# Irrigatron.net
KiCad netlist of a schematic drawn in EasyEDA
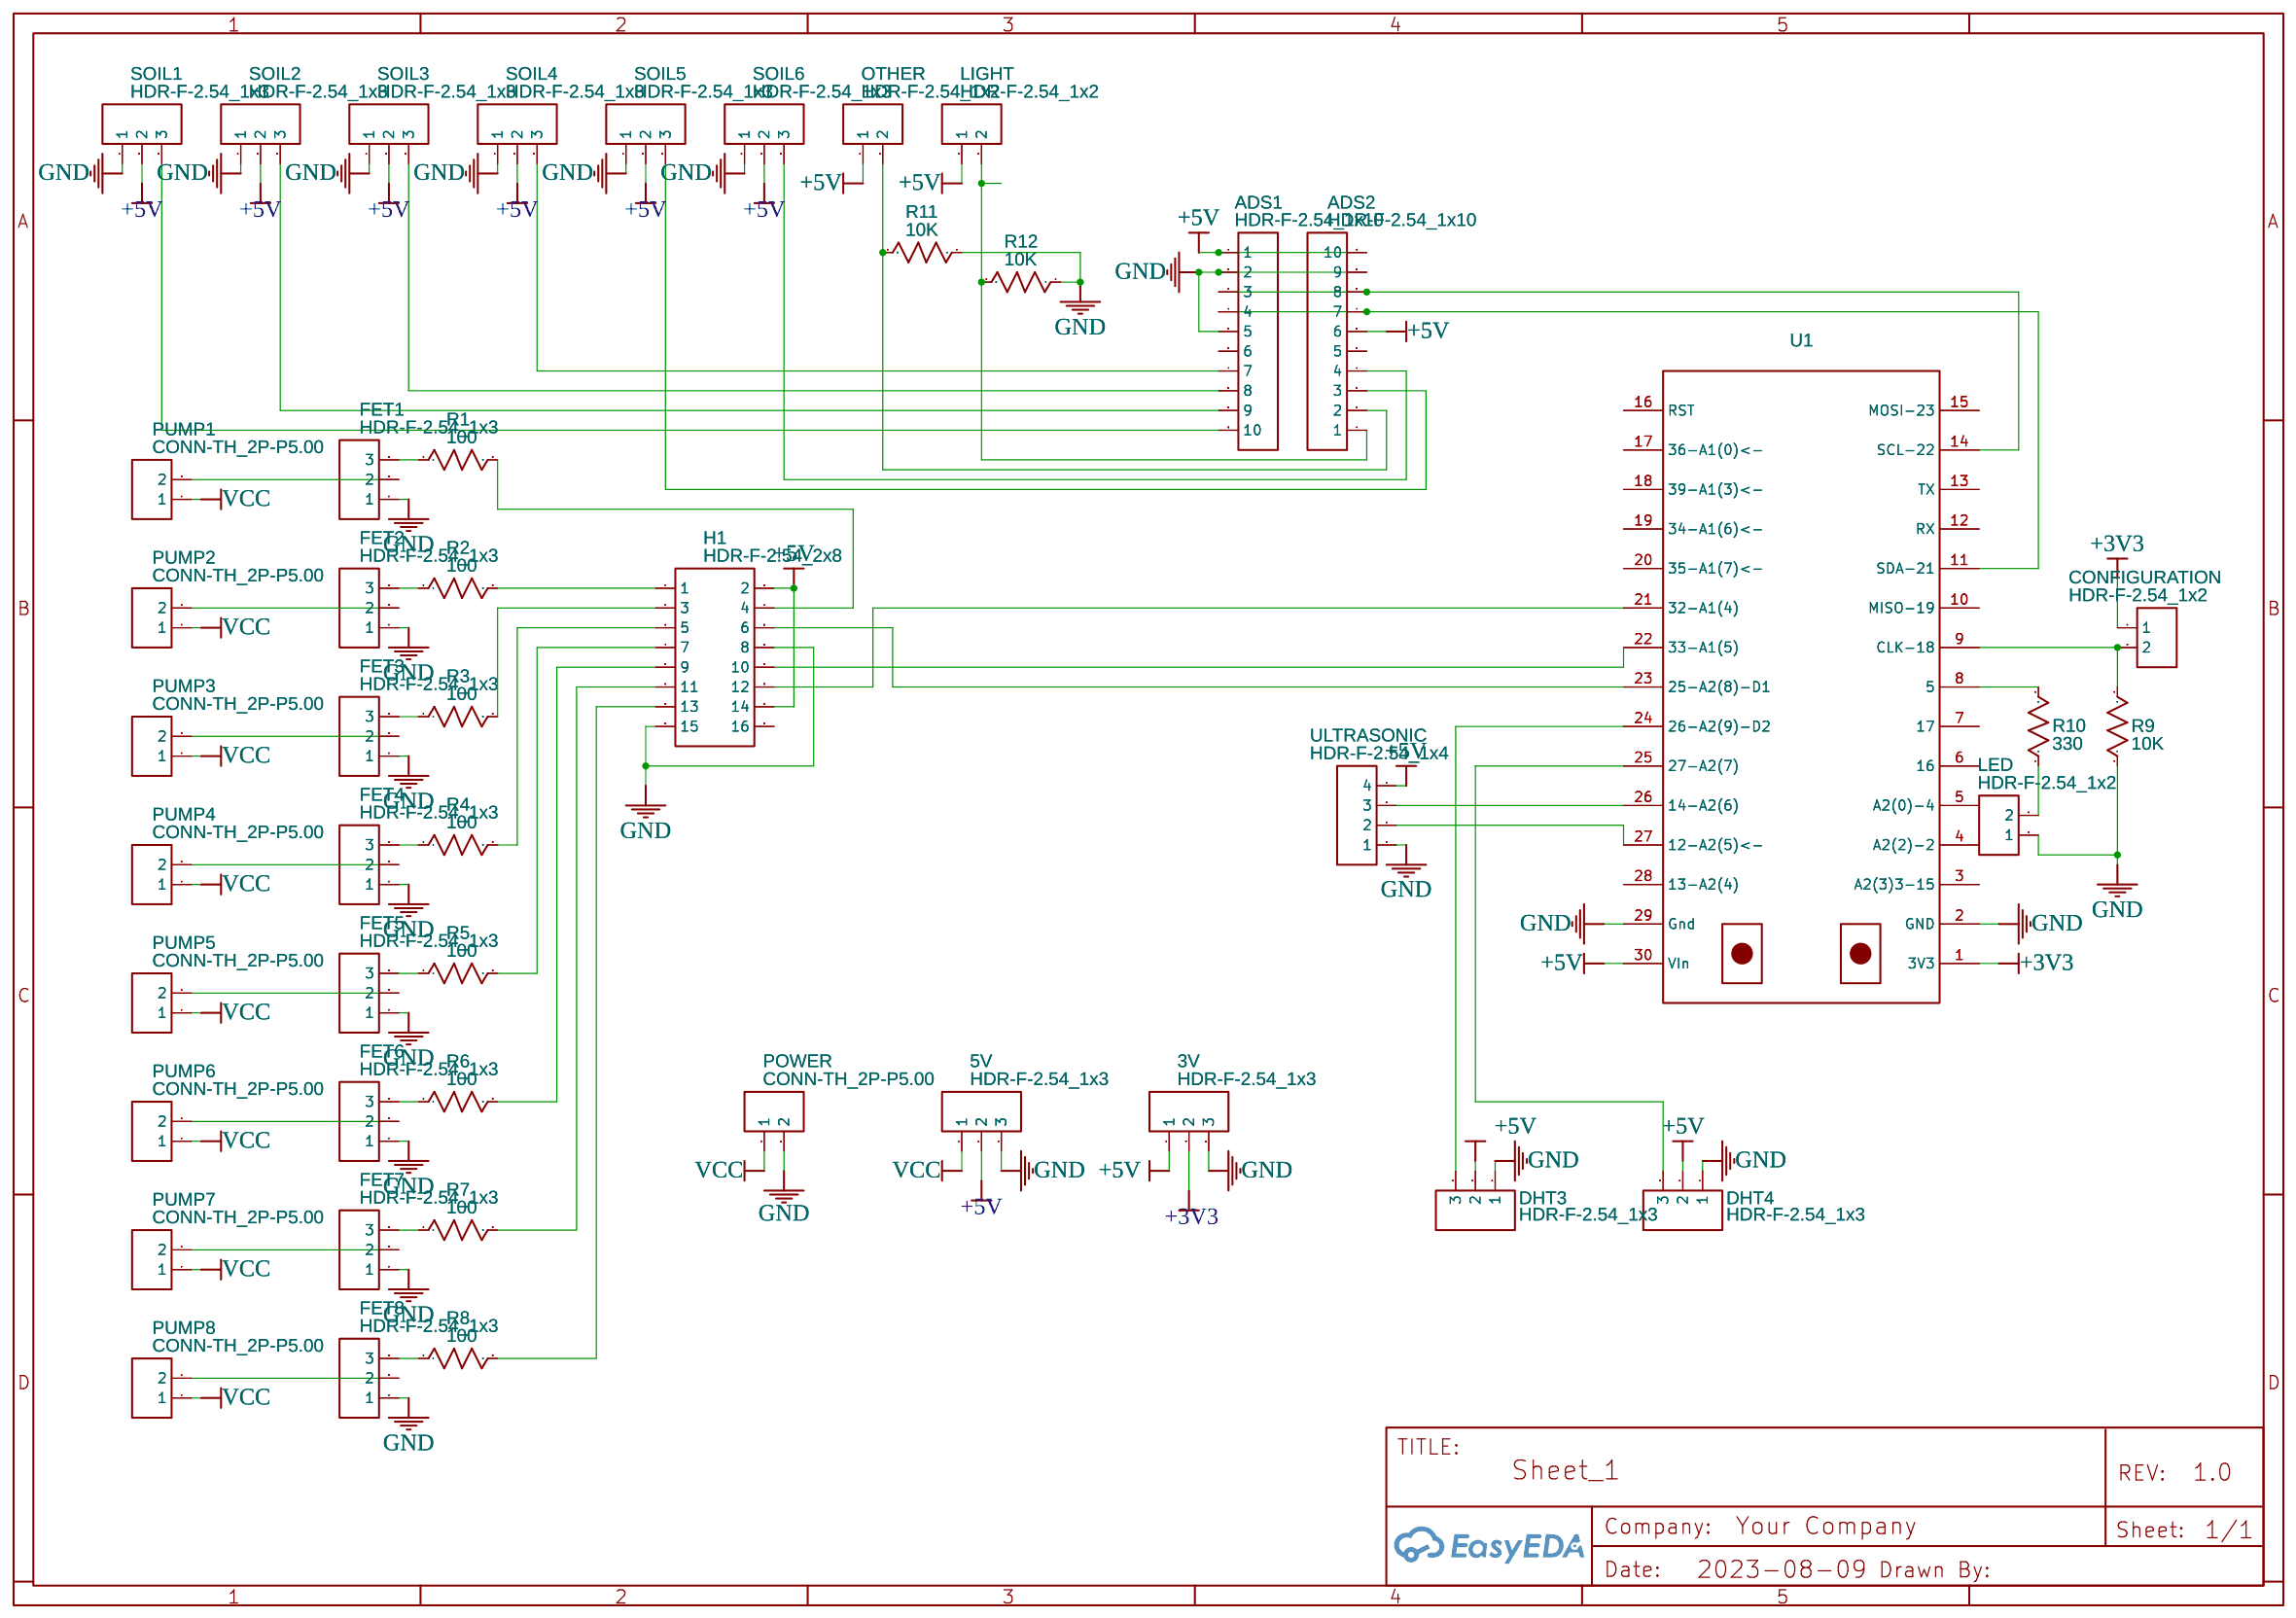
[diagram p0: schematic sheet]

(export (version "E")
  (design (tool "Eeschema 10.0.6"))
  (components
    (comp (ref "3V") (value "HDR-F-2.54_1x3") (libsource (lib "") (part "HDR-F-2.54_1x3_4")))
    (comp (ref "5V") (value "HDR-F-2.54_1x3") (libsource (lib "") (part "HDR-F-2.54_1x3_2")))
    (comp (ref "ADS1") (value "HDR-F-2.54_1x10") (libsource (lib "") (part "HDR-F-2.54_1x10_1")))
    (comp (ref "ADS2") (value "HDR-F-2.54_1x10") (libsource (lib "") (part "HDR-F-2.54_1x10")))
    (comp (ref "CONFIGURATION") (value "HDR-F-2.54_1x2") (libsource (lib "") (part "HDR-F-2.54_1x2_2")))
    (comp (ref "DHT3") (value "HDR-F-2.54_1x3") (libsource (lib "") (part "HDR-F-2.54_1x3")))
    (comp (ref "DHT4") (value "HDR-F-2.54_1x3") (libsource (lib "") (part "HDR-F-2.54_1x3")))
    (comp (ref "FET1") (value "HDR-F-2.54_1x3") (libsource (lib "") (part "HDR-F-2.54_1x3_3")))
    (comp (ref "FET2") (value "HDR-F-2.54_1x3") (libsource (lib "") (part "HDR-F-2.54_1x3_3")))
    (comp (ref "FET3") (value "HDR-F-2.54_1x3") (libsource (lib "") (part "HDR-F-2.54_1x3_3")))
    (comp (ref "FET4") (value "HDR-F-2.54_1x3") (libsource (lib "") (part "HDR-F-2.54_1x3_3")))
    (comp (ref "FET5") (value "HDR-F-2.54_1x3") (libsource (lib "") (part "HDR-F-2.54_1x3_3")))
    (comp (ref "FET6") (value "HDR-F-2.54_1x3") (libsource (lib "") (part "HDR-F-2.54_1x3_3")))
    (comp (ref "FET7") (value "HDR-F-2.54_1x3") (libsource (lib "") (part "HDR-F-2.54_1x3_3")))
    (comp (ref "FET8") (value "HDR-F-2.54_1x3") (libsource (lib "") (part "HDR-F-2.54_1x3_3")))
    (comp (ref "H1") (value "HDR-F-2.54_2x8") (libsource (lib "") (part "HDR-F-2.54_2x8")))
    (comp (ref "LED") (value "HDR-F-2.54_1x2") (libsource (lib "") (part "HDR-F-2.54_1x2")))
    (comp (ref "LIGHT") (value "HDR-F-2.54_1x2") (libsource (lib "") (part "HDR-F-2.54_1x2_1")))
    (comp (ref "OTHER") (value "HDR-F-2.54_1x2") (libsource (lib "") (part "HDR-F-2.54_1x2_3")))
    (comp (ref "POWER") (value "CONN-TH_2P-P5.00") (libsource (lib "") (part "CONN-TH_2P-P5.00_1")))
    (comp (ref "PUMP1") (value "CONN-TH_2P-P5.00") (libsource (lib "") (part "CONN-TH_2P-P5.00")))
    (comp (ref "PUMP2") (value "CONN-TH_2P-P5.00") (libsource (lib "") (part "CONN-TH_2P-P5.00")))
    (comp (ref "PUMP3") (value "CONN-TH_2P-P5.00") (libsource (lib "") (part "CONN-TH_2P-P5.00")))
    (comp (ref "PUMP4") (value "CONN-TH_2P-P5.00") (libsource (lib "") (part "CONN-TH_2P-P5.00")))
    (comp (ref "PUMP5") (value "CONN-TH_2P-P5.00") (libsource (lib "") (part "CONN-TH_2P-P5.00")))
    (comp (ref "PUMP6") (value "CONN-TH_2P-P5.00") (libsource (lib "") (part "CONN-TH_2P-P5.00")))
    (comp (ref "PUMP7") (value "CONN-TH_2P-P5.00") (libsource (lib "") (part "CONN-TH_2P-P5.00")))
    (comp (ref "PUMP8") (value "CONN-TH_2P-P5.00") (libsource (lib "") (part "CONN-TH_2P-P5.00")))
    (comp (ref "R1") (value "100") (libsource (lib "") (part "R_0603_US")))
    (comp (ref "R2") (value "100") (libsource (lib "") (part "R_0603_US")))
    (comp (ref "R3") (value "100") (libsource (lib "") (part "R_0603_US")))
    (comp (ref "R4") (value "100") (libsource (lib "") (part "R_0603_US")))
    (comp (ref "R5") (value "100") (libsource (lib "") (part "R_0603_US")))
    (comp (ref "R6") (value "100") (libsource (lib "") (part "R_0603_US")))
    (comp (ref "R7") (value "100") (libsource (lib "") (part "R_0603_US")))
    (comp (ref "R8") (value "100") (libsource (lib "") (part "R_0603_US")))
    (comp (ref "R9") (value "10K") (libsource (lib "") (part "R_0603_US_1")))
    (comp (ref "R10") (value "330") (libsource (lib "") (part "R_0603_US_1")))
    (comp (ref "R11") (value "10K") (libsource (lib "") (part "R_0603_US_2")))
    (comp (ref "R12") (value "10K") (libsource (lib "") (part "R_0603_US_2")))
    (comp (ref "SOIL1") (value "HDR-F-2.54_1x3") (libsource (lib "") (part "HDR-F-2.54_1x3_1")))
    (comp (ref "SOIL2") (value "HDR-F-2.54_1x3") (libsource (lib "") (part "HDR-F-2.54_1x3_1")))
    (comp (ref "SOIL3") (value "HDR-F-2.54_1x3") (libsource (lib "") (part "HDR-F-2.54_1x3_1")))
    (comp (ref "SOIL4") (value "HDR-F-2.54_1x3") (libsource (lib "") (part "HDR-F-2.54_1x3_1")))
    (comp (ref "SOIL5") (value "HDR-F-2.54_1x3") (libsource (lib "") (part "HDR-F-2.54_1x3_1")))
    (comp (ref "SOIL6") (value "HDR-F-2.54_1x3") (libsource (lib "") (part "HDR-F-2.54_1x3_1")))
    (comp (ref "U1") (value "NO") (libsource (lib "") (part "DOIT ESP32 DEVKIT V1 (30pins)")))
    (comp (ref "ULTRASONIC") (value "HDR-F-2.54_1x4") (libsource (lib "") (part "HDR-F-2.54_1x4")))
  )
  (nets
    (net (code "1") (name "+3V3") (class "Default")
      (node (ref "3V") (pin "2") (pinfunction "2_2") (pintype "input"))
      (node (ref "CONFIGURATION") (pin "1") (pinfunction "1_1") (pintype "input"))
      (node (ref "U1") (pin "1") (pinfunction "3V3_1") (pintype "unspecified"))
    )
    (net (code "2") (name "+5V") (class "Default")
      (node (ref "3V") (pin "1") (pinfunction "1_1") (pintype "input"))
      (node (ref "5V") (pin "2") (pinfunction "2_2") (pintype "input"))
      (node (ref "ADS1") (pin "1") (pinfunction "1_1") (pintype "unspecified"))
      (node (ref "ADS2") (pin "10") (pinfunction "10_10") (pintype "unspecified"))
      (node (ref "ADS2") (pin "6") (pinfunction "6_6") (pintype "unspecified"))
      (node (ref "DHT3") (pin "2") (pinfunction "2_2") (pintype "input"))
      (node (ref "DHT4") (pin "2") (pinfunction "2_2") (pintype "input"))
      (node (ref "H1") (pin "14") (pinfunction "14_14") (pintype "input"))
      (node (ref "H1") (pin "2") (pinfunction "2_2") (pintype "input"))
      (node (ref "LIGHT") (pin "1") (pinfunction "1_1") (pintype "input"))
      (node (ref "OTHER") (pin "1") (pinfunction "1_1") (pintype "input"))
      (node (ref "SOIL1") (pin "2") (pinfunction "2_2") (pintype "input"))
      (node (ref "SOIL2") (pin "2") (pinfunction "2_2") (pintype "input"))
      (node (ref "SOIL3") (pin "2") (pinfunction "2_2") (pintype "input"))
      (node (ref "SOIL4") (pin "2") (pinfunction "2_2") (pintype "input"))
      (node (ref "SOIL5") (pin "2") (pinfunction "2_2") (pintype "input"))
      (node (ref "SOIL6") (pin "2") (pinfunction "2_2") (pintype "input"))
      (node (ref "U1") (pin "30") (pinfunction "VIn_30") (pintype "unspecified"))
      (node (ref "ULTRASONIC") (pin "4") (pinfunction "4_4") (pintype "unspecified"))
    )
    (net (code "3") (name "GND") (class "Default")
      (node (ref "3V") (pin "3") (pinfunction "3_3") (pintype "input"))
      (node (ref "5V") (pin "3") (pinfunction "3_3") (pintype "input"))
      (node (ref "ADS1") (pin "2") (pinfunction "2_2") (pintype "unspecified"))
      (node (ref "ADS1") (pin "5") (pinfunction "5_5") (pintype "unspecified"))
      (node (ref "ADS2") (pin "9") (pinfunction "9_9") (pintype "unspecified"))
      (node (ref "DHT3") (pin "1") (pinfunction "1_1") (pintype "input"))
      (node (ref "DHT4") (pin "1") (pinfunction "1_1") (pintype "input"))
      (node (ref "FET1") (pin "1") (pinfunction "1_1") (pintype "input"))
      (node (ref "FET2") (pin "1") (pinfunction "1_1") (pintype "input"))
      (node (ref "FET3") (pin "1") (pinfunction "1_1") (pintype "input"))
      (node (ref "FET4") (pin "1") (pinfunction "1_1") (pintype "input"))
      (node (ref "FET5") (pin "1") (pinfunction "1_1") (pintype "input"))
      (node (ref "FET6") (pin "1") (pinfunction "1_1") (pintype "input"))
      (node (ref "FET7") (pin "1") (pinfunction "1_1") (pintype "input"))
      (node (ref "FET8") (pin "1") (pinfunction "1_1") (pintype "input"))
      (node (ref "H1") (pin "15") (pinfunction "15_15") (pintype "input"))
      (node (ref "H1") (pin "8") (pinfunction "8_8") (pintype "input"))
      (node (ref "LED") (pin "1") (pinfunction "1_1") (pintype "input"))
      (node (ref "POWER") (pin "2") (pinfunction "2_2") (pintype "unspecified"))
      (node (ref "R11") (pin "1") (pinfunction "1_1") (pintype "unspecified"))
      (node (ref "R12") (pin "1") (pinfunction "1_1") (pintype "unspecified"))
      (node (ref "R9") (pin "1") (pinfunction "1_1") (pintype "unspecified"))
      (node (ref "SOIL1") (pin "1") (pinfunction "1_1") (pintype "input"))
      (node (ref "SOIL2") (pin "1") (pinfunction "1_1") (pintype "input"))
      (node (ref "SOIL3") (pin "1") (pinfunction "1_1") (pintype "input"))
      (node (ref "SOIL4") (pin "1") (pinfunction "1_1") (pintype "input"))
      (node (ref "SOIL5") (pin "1") (pinfunction "1_1") (pintype "input"))
      (node (ref "SOIL6") (pin "1") (pinfunction "1_1") (pintype "input"))
      (node (ref "U1") (pin "2") (pinfunction "GND_2") (pintype "unspecified"))
      (node (ref "U1") (pin "29") (pinfunction "Gnd_29") (pintype "unspecified"))
      (node (ref "ULTRASONIC") (pin "1") (pinfunction "1_1") (pintype "unspecified"))
    )
    (net (code "4") (name "Net-(ADS1-Pad7)") (class "Default")
      (node (ref "ADS1") (pin "7") (pinfunction "7_7") (pintype "unspecified"))
      (node (ref "SOIL4") (pin "3") (pinfunction "3_3") (pintype "input"))
    )
    (net (code "5") (name "Net-(ADS1-Pad8)") (class "Default")
      (node (ref "ADS1") (pin "8") (pinfunction "8_8") (pintype "unspecified"))
      (node (ref "SOIL3") (pin "3") (pinfunction "3_3") (pintype "input"))
    )
    (net (code "6") (name "Net-(ADS1-Pad9)") (class "Default")
      (node (ref "ADS1") (pin "9") (pinfunction "9_9") (pintype "unspecified"))
      (node (ref "SOIL2") (pin "3") (pinfunction "3_3") (pintype "input"))
    )
    (net (code "7") (name "Net-(ADS1-Pad10)") (class "Default")
      (node (ref "ADS1") (pin "10") (pinfunction "10_10") (pintype "unspecified"))
      (node (ref "SOIL1") (pin "3") (pinfunction "3_3") (pintype "input"))
    )
    (net (code "8") (name "Net-(ADS2-Pad1)") (class "Default")
      (node (ref "ADS2") (pin "1") (pinfunction "1_1") (pintype "unspecified"))
      (node (ref "LIGHT") (pin "2") (pinfunction "2_2") (pintype "input"))
      (node (ref "R12") (pin "2") (pinfunction "2_2") (pintype "unspecified"))
    )
    (net (code "9") (name "Net-(ADS2-Pad2)") (class "Default")
      (node (ref "ADS2") (pin "2") (pinfunction "2_2") (pintype "unspecified"))
      (node (ref "OTHER") (pin "2") (pinfunction "2_2") (pintype "input"))
      (node (ref "R11") (pin "2") (pinfunction "2_2") (pintype "unspecified"))
    )
    (net (code "10") (name "Net-(ADS2-Pad3)") (class "Default")
      (node (ref "ADS2") (pin "3") (pinfunction "3_3") (pintype "unspecified"))
      (node (ref "SOIL5") (pin "3") (pinfunction "3_3") (pintype "input"))
    )
    (net (code "11") (name "Net-(ADS2-Pad4)") (class "Default")
      (node (ref "ADS2") (pin "4") (pinfunction "4_4") (pintype "unspecified"))
      (node (ref "SOIL6") (pin "3") (pinfunction "3_3") (pintype "input"))
    )
    (net (code "12") (name "Net-(FET1-Pad2)") (class "Default")
      (node (ref "FET1") (pin "2") (pinfunction "2_2") (pintype "input"))
      (node (ref "PUMP1") (pin "2") (pinfunction "2_2") (pintype "unspecified"))
    )
    (net (code "13") (name "Net-(FET1-Pad3)") (class "Default")
      (node (ref "FET1") (pin "3") (pinfunction "3_3") (pintype "input"))
      (node (ref "R1") (pin "1") (pinfunction "1_1") (pintype "unspecified"))
    )
    (net (code "14") (name "Net-(FET2-Pad2)") (class "Default")
      (node (ref "FET2") (pin "2") (pinfunction "2_2") (pintype "input"))
      (node (ref "PUMP2") (pin "2") (pinfunction "2_2") (pintype "unspecified"))
    )
    (net (code "15") (name "Net-(FET2-Pad3)") (class "Default")
      (node (ref "FET2") (pin "3") (pinfunction "3_3") (pintype "input"))
      (node (ref "R2") (pin "1") (pinfunction "1_1") (pintype "unspecified"))
    )
    (net (code "16") (name "Net-(FET3-Pad2)") (class "Default")
      (node (ref "FET3") (pin "2") (pinfunction "2_2") (pintype "input"))
      (node (ref "PUMP3") (pin "2") (pinfunction "2_2") (pintype "unspecified"))
    )
    (net (code "17") (name "Net-(FET3-Pad3)") (class "Default")
      (node (ref "FET3") (pin "3") (pinfunction "3_3") (pintype "input"))
      (node (ref "R3") (pin "1") (pinfunction "1_1") (pintype "unspecified"))
    )
    (net (code "18") (name "Net-(FET4-Pad2)") (class "Default")
      (node (ref "FET4") (pin "2") (pinfunction "2_2") (pintype "input"))
      (node (ref "PUMP4") (pin "2") (pinfunction "2_2") (pintype "unspecified"))
    )
    (net (code "19") (name "Net-(FET4-Pad3)") (class "Default")
      (node (ref "FET4") (pin "3") (pinfunction "3_3") (pintype "input"))
      (node (ref "R4") (pin "1") (pinfunction "1_1") (pintype "unspecified"))
    )
    (net (code "20") (name "Net-(FET5-Pad2)") (class "Default")
      (node (ref "FET5") (pin "2") (pinfunction "2_2") (pintype "input"))
      (node (ref "PUMP5") (pin "2") (pinfunction "2_2") (pintype "unspecified"))
    )
    (net (code "21") (name "Net-(FET5-Pad3)") (class "Default")
      (node (ref "FET5") (pin "3") (pinfunction "3_3") (pintype "input"))
      (node (ref "R5") (pin "1") (pinfunction "1_1") (pintype "unspecified"))
    )
    (net (code "22") (name "Net-(FET6-Pad2)") (class "Default")
      (node (ref "FET6") (pin "2") (pinfunction "2_2") (pintype "input"))
      (node (ref "PUMP6") (pin "2") (pinfunction "2_2") (pintype "unspecified"))
    )
    (net (code "23") (name "Net-(FET6-Pad3)") (class "Default")
      (node (ref "FET6") (pin "3") (pinfunction "3_3") (pintype "input"))
      (node (ref "R6") (pin "1") (pinfunction "1_1") (pintype "unspecified"))
    )
    (net (code "24") (name "Net-(FET7-Pad2)") (class "Default")
      (node (ref "FET7") (pin "2") (pinfunction "2_2") (pintype "input"))
      (node (ref "PUMP7") (pin "2") (pinfunction "2_2") (pintype "unspecified"))
    )
    (net (code "25") (name "Net-(FET7-Pad3)") (class "Default")
      (node (ref "FET7") (pin "3") (pinfunction "3_3") (pintype "input"))
      (node (ref "R7") (pin "1") (pinfunction "1_1") (pintype "unspecified"))
    )
    (net (code "26") (name "Net-(FET8-Pad2)") (class "Default")
      (node (ref "FET8") (pin "2") (pinfunction "2_2") (pintype "input"))
      (node (ref "PUMP8") (pin "2") (pinfunction "2_2") (pintype "unspecified"))
    )
    (net (code "27") (name "Net-(FET8-Pad3)") (class "Default")
      (node (ref "FET8") (pin "3") (pinfunction "3_3") (pintype "input"))
      (node (ref "R8") (pin "1") (pinfunction "1_1") (pintype "unspecified"))
    )
    (net (code "28") (name "Net-(H1-Pad1)") (class "Default")
      (node (ref "H1") (pin "1") (pinfunction "1_1") (pintype "input"))
      (node (ref "R2") (pin "2") (pinfunction "2_2") (pintype "unspecified"))
    )
    (net (code "29") (name "Net-(H1-Pad3)") (class "Default")
      (node (ref "H1") (pin "3") (pinfunction "3_3") (pintype "input"))
      (node (ref "R3") (pin "2") (pinfunction "2_2") (pintype "unspecified"))
    )
    (net (code "30") (name "Net-(H1-Pad4)") (class "Default")
      (node (ref "H1") (pin "4") (pinfunction "4_4") (pintype "input"))
      (node (ref "R1") (pin "2") (pinfunction "2_2") (pintype "unspecified"))
    )
    (net (code "31") (name "Net-(H1-Pad5)") (class "Default")
      (node (ref "H1") (pin "5") (pinfunction "5_5") (pintype "input"))
      (node (ref "R4") (pin "2") (pinfunction "2_2") (pintype "unspecified"))
    )
    (net (code "32") (name "Net-(H1-Pad7)") (class "Default")
      (node (ref "H1") (pin "7") (pinfunction "7_7") (pintype "input"))
      (node (ref "R5") (pin "2") (pinfunction "2_2") (pintype "unspecified"))
    )
    (net (code "33") (name "Net-(H1-Pad9)") (class "Default")
      (node (ref "H1") (pin "9") (pinfunction "9_9") (pintype "input"))
      (node (ref "R6") (pin "2") (pinfunction "2_2") (pintype "unspecified"))
    )
    (net (code "34") (name "Net-(H1-Pad11)") (class "Default")
      (node (ref "H1") (pin "11") (pinfunction "11_11") (pintype "input"))
      (node (ref "R7") (pin "2") (pinfunction "2_2") (pintype "unspecified"))
    )
    (net (code "35") (name "Net-(H1-Pad13)") (class "Default")
      (node (ref "H1") (pin "13") (pinfunction "13_13") (pintype "input"))
      (node (ref "R8") (pin "2") (pinfunction "2_2") (pintype "unspecified"))
    )
    (net (code "36") (name "Net-(LED-Pad2)") (class "Default")
      (node (ref "LED") (pin "2") (pinfunction "2_2") (pintype "input"))
      (node (ref "R10") (pin "1") (pinfunction "1_1") (pintype "unspecified"))
    )
    (net (code "37") (name "Net-(U1-5)") (class "Default")
      (node (ref "R10") (pin "2") (pinfunction "2_2") (pintype "unspecified"))
      (node (ref "U1") (pin "8") (pinfunction "5_8") (pintype "unspecified"))
    )
    (net (code "38") (name "Net-(U1-12-A2(5)<-)") (class "Default")
      (node (ref "U1") (pin "27") (pinfunction "12-A2(5)<-_27") (pintype "unspecified"))
      (node (ref "ULTRASONIC") (pin "2") (pinfunction "2_2") (pintype "unspecified"))
    )
    (net (code "39") (name "Net-(U1-14-A2(6))") (class "Default")
      (node (ref "U1") (pin "26") (pinfunction "14-A2(6)_26") (pintype "unspecified"))
      (node (ref "ULTRASONIC") (pin "3") (pinfunction "3_3") (pintype "unspecified"))
    )
    (net (code "40") (name "Net-(U1-25-A2(8)-D1)") (class "Default")
      (node (ref "H1") (pin "6") (pinfunction "6_6") (pintype "input"))
      (node (ref "U1") (pin "23") (pinfunction "25-A2(8)-D1_23") (pintype "unspecified"))
    )
    (net (code "41") (name "Net-(U1-26-A2(9)-D2)") (class "Default")
      (node (ref "DHT3") (pin "3") (pinfunction "3_3") (pintype "input"))
      (node (ref "U1") (pin "24") (pinfunction "26-A2(9)-D2_24") (pintype "unspecified"))
    )
    (net (code "42") (name "Net-(U1-27-A2(7))") (class "Default")
      (node (ref "DHT4") (pin "3") (pinfunction "3_3") (pintype "input"))
      (node (ref "U1") (pin "25") (pinfunction "27-A2(7)_25") (pintype "unspecified"))
    )
    (net (code "43") (name "Net-(U1-32-A1(4))") (class "Default")
      (node (ref "H1") (pin "12") (pinfunction "12_12") (pintype "input"))
      (node (ref "U1") (pin "21") (pinfunction "32-A1(4)_21") (pintype "unspecified"))
    )
    (net (code "44") (name "Net-(U1-33-A1(5))") (class "Default")
      (node (ref "H1") (pin "10") (pinfunction "10_10") (pintype "input"))
      (node (ref "U1") (pin "22") (pinfunction "33-A1(5)_22") (pintype "unspecified"))
    )
    (net (code "45") (name "Net-(U1-CLK-18)") (class "Default")
      (node (ref "CONFIGURATION") (pin "2") (pinfunction "2_2") (pintype "input"))
      (node (ref "R9") (pin "2") (pinfunction "2_2") (pintype "unspecified"))
      (node (ref "U1") (pin "9") (pinfunction "CLK-18_9") (pintype "unspecified"))
    )
    (net (code "46") (name "Net-(U1-SCL-22)") (class "Default")
      (node (ref "ADS1") (pin "3") (pinfunction "3_3") (pintype "unspecified"))
      (node (ref "ADS2") (pin "8") (pinfunction "8_8") (pintype "unspecified"))
      (node (ref "U1") (pin "14") (pinfunction "SCL-22_14") (pintype "unspecified"))
    )
    (net (code "47") (name "Net-(U1-SDA-21)") (class "Default")
      (node (ref "ADS1") (pin "4") (pinfunction "4_4") (pintype "unspecified"))
      (node (ref "ADS2") (pin "7") (pinfunction "7_7") (pintype "unspecified"))
      (node (ref "U1") (pin "11") (pinfunction "SDA-21_11") (pintype "unspecified"))
    )
    (net (code "48") (name "VCC") (class "Default")
      (node (ref "5V") (pin "1") (pinfunction "1_1") (pintype "input"))
      (node (ref "POWER") (pin "1") (pinfunction "1_1") (pintype "unspecified"))
      (node (ref "PUMP1") (pin "1") (pinfunction "1_1") (pintype "unspecified"))
      (node (ref "PUMP2") (pin "1") (pinfunction "1_1") (pintype "unspecified"))
      (node (ref "PUMP3") (pin "1") (pinfunction "1_1") (pintype "unspecified"))
      (node (ref "PUMP4") (pin "1") (pinfunction "1_1") (pintype "unspecified"))
      (node (ref "PUMP5") (pin "1") (pinfunction "1_1") (pintype "unspecified"))
      (node (ref "PUMP6") (pin "1") (pinfunction "1_1") (pintype "unspecified"))
      (node (ref "PUMP7") (pin "1") (pinfunction "1_1") (pintype "unspecified"))
      (node (ref "PUMP8") (pin "1") (pinfunction "1_1") (pintype "unspecified"))
    )
    (net (code "49") (name "unconnected-(ADS1-Pad6)") (class "Default")
      (node (ref "ADS1") (pin "6") (pinfunction "6_6") (pintype "unspecified"))
    )
    (net (code "50") (name "unconnected-(ADS2-Pad5)") (class "Default")
      (node (ref "ADS2") (pin "5") (pinfunction "5_5") (pintype "unspecified"))
    )
    (net (code "51") (name "unconnected-(H1-Pad16)") (class "Default")
      (node (ref "H1") (pin "16") (pinfunction "16_16") (pintype "input"))
    )
    (net (code "52") (name "unconnected-(U1-13-A2(4)-Pad28)") (class "Default")
      (node (ref "U1") (pin "28") (pinfunction "13-A2(4)_28") (pintype "unspecified"))
    )
    (net (code "53") (name "unconnected-(U1-16-Pad6)") (class "Default")
      (node (ref "U1") (pin "6") (pinfunction "16_6") (pintype "unspecified"))
    )
    (net (code "54") (name "unconnected-(U1-17-Pad7)") (class "Default")
      (node (ref "U1") (pin "7") (pinfunction "17_7") (pintype "unspecified"))
    )
    (net (code "55") (name "unconnected-(U1-34-A1(6)<--Pad19)") (class "Default")
      (node (ref "U1") (pin "19") (pinfunction "34-A1(6)<-_19") (pintype "unspecified"))
    )
    (net (code "56") (name "unconnected-(U1-35-A1(7)<--Pad20)") (class "Default")
      (node (ref "U1") (pin "20") (pinfunction "35-A1(7)<-_20") (pintype "unspecified"))
    )
    (net (code "57") (name "unconnected-(U1-36-A1(0)<--Pad17)") (class "Default")
      (node (ref "U1") (pin "17") (pinfunction "36-A1(0)<-_17") (pintype "unspecified"))
    )
    (net (code "58") (name "unconnected-(U1-39-A1(3)<--Pad18)") (class "Default")
      (node (ref "U1") (pin "18") (pinfunction "39-A1(3)<-_18") (pintype "unspecified"))
    )
    (net (code "59") (name "unconnected-(U1-A2(0)-4-Pad5)") (class "Default")
      (node (ref "U1") (pin "5") (pinfunction "A2(0)-4_5") (pintype "unspecified"))
    )
    (net (code "60") (name "unconnected-(U1-A2(2)-2-Pad4)") (class "Default")
      (node (ref "U1") (pin "4") (pinfunction "A2(2)-2_4") (pintype "unspecified"))
    )
    (net (code "61") (name "unconnected-(U1-A2(3)3-15-Pad3)") (class "Default")
      (node (ref "U1") (pin "3") (pinfunction "A2(3)3-15_3") (pintype "unspecified"))
    )
    (net (code "62") (name "unconnected-(U1-MISO-19-Pad10)") (class "Default")
      (node (ref "U1") (pin "10") (pinfunction "MISO-19_10") (pintype "unspecified"))
    )
    (net (code "63") (name "unconnected-(U1-MOSI-23-Pad15)") (class "Default")
      (node (ref "U1") (pin "15") (pinfunction "MOSI-23_15") (pintype "unspecified"))
    )
    (net (code "64") (name "unconnected-(U1-RST-Pad16)") (class "Default")
      (node (ref "U1") (pin "16") (pinfunction "RST_16") (pintype "unspecified"))
    )
    (net (code "65") (name "unconnected-(U1-RX-Pad12)") (class "Default")
      (node (ref "U1") (pin "12") (pinfunction "RX_12") (pintype "unspecified"))
    )
    (net (code "66") (name "unconnected-(U1-TX-Pad13)") (class "Default")
      (node (ref "U1") (pin "13") (pinfunction "TX_13") (pintype "unspecified"))
    )
  )
)
